# XoverVolume.net
KiCad netlist of a schematic drawn in EAGLE
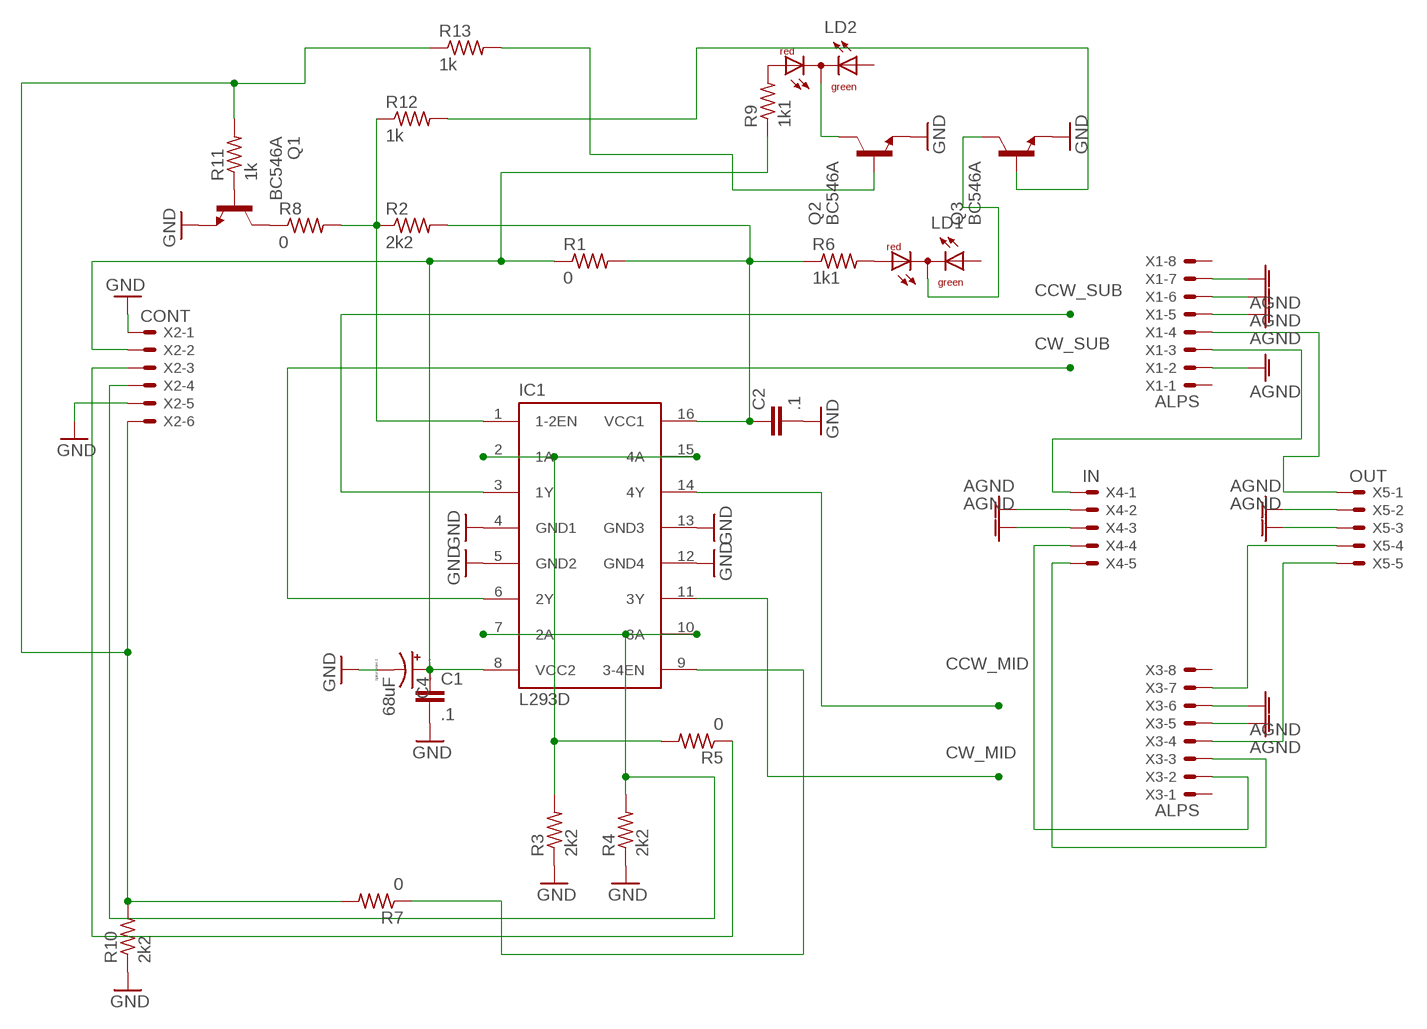
[diagram p0: schematic, sheet 1]

(export (version "E")
  (design (tool "Eeschema 10.0.6"))
  (components
    (comp (ref "C1")
      (value ".1")
      (footprint "eagle-import:C1210")
      (libsource (lib "eagle-import") (part "C-EUC1210"))
    )
    (comp (ref "C2")
      (value ".1")
      (footprint "eagle-import:C1210")
      (libsource (lib "eagle-import") (part "C-EUC1210"))
    )
    (comp (ref "C4")
      (value "68uF")
      (footprint "eagle-import:E2,5-6E")
      (libsource (lib "eagle-import") (part "CPOL-USE2,5-6E"))
    )
    (comp (ref "IC1")
      (value "L293D")
      (footprint "eagle-import:DIL16")
      (libsource (lib "eagle-import") (part "L293D"))
    )
    (comp (ref "LD1")
      (value "DUOLED-RG-C")
      (footprint "eagle-import:DUOLED-C-5MM")
      (libsource (lib "eagle-import") (part "DUOLED-RG-C"))
    )
    (comp (ref "LD2")
      (value "DUOLED-RG-C")
      (footprint "eagle-import:DUOLED-C-5MM")
      (libsource (lib "eagle-import") (part "DUOLED-RG-C"))
    )
    (comp (ref "Q1")
      (value "BC546A")
      (footprint "eagle-import:TO92-EBC")
      (libsource (lib "eagle-import") (part "BC546A"))
    )
    (comp (ref "Q2")
      (value "BC546A")
      (footprint "eagle-import:TO92-EBC")
      (libsource (lib "eagle-import") (part "BC546A"))
    )
    (comp (ref "Q3")
      (value "BC546A")
      (footprint "eagle-import:TO92-EBC")
      (libsource (lib "eagle-import") (part "BC546A"))
    )
    (comp (ref "R1")
      (value "0")
      (footprint "eagle-import:0207_15")
      (libsource (lib "eagle-import") (part "R-US_0207/15"))
    )
    (comp (ref "R2")
      (value "2k2")
      (footprint "eagle-import:R1210")
      (libsource (lib "eagle-import") (part "R-US_R1210"))
    )
    (comp (ref "R3")
      (value "2k2")
      (footprint "eagle-import:R1210")
      (libsource (lib "eagle-import") (part "R-US_R1210"))
    )
    (comp (ref "R4")
      (value "2k2")
      (footprint "eagle-import:R1210")
      (libsource (lib "eagle-import") (part "R-US_R1210"))
    )
    (comp (ref "R5")
      (value "0")
      (footprint "eagle-import:0309_12")
      (libsource (lib "eagle-import") (part "R-US_0309/12"))
    )
    (comp (ref "R6")
      (value "1k1")
      (footprint "eagle-import:0309_12")
      (libsource (lib "eagle-import") (part "R-US_0309/12"))
    )
    (comp (ref "R7")
      (value "0")
      (footprint "eagle-import:0309_12")
      (libsource (lib "eagle-import") (part "R-US_0309/12"))
    )
    (comp (ref "R8")
      (value "0")
      (footprint "eagle-import:0207_15")
      (libsource (lib "eagle-import") (part "R-US_0207/15"))
    )
    (comp (ref "R9")
      (value "1k1")
      (footprint "eagle-import:0309_12")
      (libsource (lib "eagle-import") (part "R-US_0309/12"))
    )
    (comp (ref "R10")
      (value "2k2")
      (footprint "eagle-import:R1210")
      (libsource (lib "eagle-import") (part "R-US_R1210"))
    )
    (comp (ref "R11")
      (value "1k")
      (footprint "eagle-import:0207_5V")
      (libsource (lib "eagle-import") (part "R-US_0207/5V"))
    )
    (comp (ref "R12")
      (value "1k")
      (footprint "eagle-import:0204_5")
      (libsource (lib "eagle-import") (part "R-US_0204/5"))
    )
    (comp (ref "R13")
      (value "1k")
      (footprint "eagle-import:R1210")
      (libsource (lib "eagle-import") (part "R-US_R1210"))
    )
    (comp (ref "X1")
      (value "ALPS")
      (footprint "eagle-import:22-23-2081")
      (fields (field (name "MF") "MOLEX") (field (name "MPN") "22-23-2081"))
      (libsource (lib "eagle-import") (part "22-23-2081"))
    )
    (comp (ref "X2")
      (value "CONT")
      (footprint "eagle-import:22-23-2061")
      (fields (field (name "MF") "MOLEX") (field (name "MPN") "22-23-2061"))
      (libsource (lib "eagle-import") (part "22-23-2061"))
    )
    (comp (ref "X3")
      (value "ALPS")
      (footprint "eagle-import:22-23-2081")
      (fields (field (name "MF") "MOLEX") (field (name "MPN") "22-23-2081"))
      (libsource (lib "eagle-import") (part "22-23-2081"))
    )
    (comp (ref "X4")
      (value "IN")
      (footprint "eagle-import:22-23-2051")
      (fields (field (name "MF") "MOLEX") (field (name "MPN") "22-23-2051"))
      (libsource (lib "eagle-import") (part "22-23-2051"))
    )
    (comp (ref "X5")
      (value "OUT")
      (footprint "eagle-import:22-23-2051")
      (fields (field (name "MF") "MOLEX") (field (name "MPN") "22-23-2051"))
      (libsource (lib "eagle-import") (part "22-23-2051"))
    )
  )
  (nets
    (net (code "1") (name "/CCW_MID") (class "Default")
      (node (ref "IC1") (pin "14") (pinfunction "4Y_14") (pintype "output"))
    )
    (net (code "2") (name "/CCW_SUB") (class "Default")
      (node (ref "IC1") (pin "3") (pinfunction "1Y_3") (pintype "output"))
    )
    (net (code "3") (name "/CW_MID") (class "Default")
      (node (ref "IC1") (pin "11") (pinfunction "3Y_11") (pintype "output"))
    )
    (net (code "4") (name "/CW_SUB") (class "Default")
      (node (ref "IC1") (pin "6") (pinfunction "2Y_6") (pintype "output"))
    )
    (net (code "5") (name "AGND") (class "Default")
      (node (ref "X1") (pin "2") (pinfunction "S_2") (pintype "passive"))
      (node (ref "X1") (pin "5") (pinfunction "S_5") (pintype "passive"))
      (node (ref "X1") (pin "6") (pinfunction "S_6") (pintype "passive"))
      (node (ref "X1") (pin "7") (pinfunction "S_7") (pintype "passive"))
      (node (ref "X3") (pin "5") (pinfunction "S_5") (pintype "passive"))
      (node (ref "X3") (pin "6") (pinfunction "S_6") (pintype "passive"))
      (node (ref "X4") (pin "2") (pinfunction "S_2") (pintype "passive"))
      (node (ref "X4") (pin "3") (pinfunction "S_3") (pintype "passive"))
      (node (ref "X5") (pin "2") (pinfunction "S_2") (pintype "passive"))
      (node (ref "X5") (pin "3") (pinfunction "S_3") (pintype "passive"))
    )
    (net (code "6") (name "GND") (class "Default")
      (node (ref "C1") (pin "2") (pinfunction "2_2") (pintype "passive"))
      (node (ref "C2") (pin "2") (pinfunction "2_2") (pintype "passive"))
      (node (ref "C4") (pin "-") (pinfunction "-_-") (pintype "passive"))
      (node (ref "IC1") (pin "12") (pinfunction "GND4_12") (pintype "power_in"))
      (node (ref "IC1") (pin "13") (pinfunction "GND3_13") (pintype "power_in"))
      (node (ref "IC1") (pin "4") (pinfunction "GND1_4") (pintype "power_in"))
      (node (ref "IC1") (pin "5") (pinfunction "GND2_5") (pintype "power_in"))
      (node (ref "Q1") (pin "E") (pinfunction "E_E") (pintype "passive"))
      (node (ref "Q2") (pin "E") (pinfunction "E_E") (pintype "passive"))
      (node (ref "Q3") (pin "E") (pinfunction "E_E") (pintype "passive"))
      (node (ref "R10") (pin "1") (pinfunction "1_1") (pintype "passive"))
      (node (ref "R3") (pin "1") (pinfunction "1_1") (pintype "passive"))
      (node (ref "R4") (pin "1") (pinfunction "1_1") (pintype "passive"))
      (node (ref "X2") (pin "1") (pinfunction "S_1") (pintype "passive"))
      (node (ref "X2") (pin "5") (pinfunction "S_5") (pintype "passive"))
    )
    (net (code "7") (name "Net-(IC1-1-2EN)") (class "Default")
      (node (ref "IC1") (pin "1") (pinfunction "1-2EN_1") (pintype "input"))
      (node (ref "R12") (pin "1") (pinfunction "1_1") (pintype "passive"))
      (node (ref "R2") (pin "1") (pinfunction "1_1") (pintype "passive"))
      (node (ref "R8") (pin "2") (pinfunction "2_2") (pintype "passive"))
    )
    (net (code "8") (name "Net-(IC1-1A)") (class "Default")
      (node (ref "IC1") (pin "15") (pinfunction "4A_15") (pintype "input"))
      (node (ref "IC1") (pin "2") (pinfunction "1A_2") (pintype "input"))
      (node (ref "R3") (pin "2") (pinfunction "2_2") (pintype "passive"))
      (node (ref "R5") (pin "2") (pinfunction "2_2") (pintype "passive"))
    )
    (net (code "9") (name "Net-(IC1-2A)") (class "Default")
      (node (ref "IC1") (pin "10") (pinfunction "3A_10") (pintype "input"))
      (node (ref "IC1") (pin "7") (pinfunction "2A_7") (pintype "input"))
      (node (ref "R4") (pin "2") (pinfunction "2_2") (pintype "passive"))
      (node (ref "X2") (pin "4") (pinfunction "S_4") (pintype "passive"))
    )
    (net (code "10") (name "Net-(IC1-3-4EN)") (class "Default")
      (node (ref "IC1") (pin "9") (pinfunction "3-4EN_9") (pintype "input"))
      (node (ref "R7") (pin "1") (pinfunction "1_1") (pintype "passive"))
    )
    (net (code "11") (name "Net-(IC1-VCC1)") (class "Default")
      (node (ref "C2") (pin "1") (pinfunction "1_1") (pintype "passive"))
      (node (ref "IC1") (pin "16") (pinfunction "VCC1_16") (pintype "power_in"))
      (node (ref "R1") (pin "2") (pinfunction "2_2") (pintype "passive"))
      (node (ref "R2") (pin "2") (pinfunction "2_2") (pintype "passive"))
      (node (ref "R6") (pin "1") (pinfunction "1_1") (pintype "passive"))
    )
    (net (code "12") (name "Net-(IC1-VCC2)") (class "Default")
      (node (ref "C1") (pin "1") (pinfunction "1_1") (pintype "passive"))
      (node (ref "C4") (pin "+") (pinfunction "+_+") (pintype "passive"))
      (node (ref "IC1") (pin "8") (pinfunction "VCC2_8") (pintype "power_in"))
      (node (ref "R1") (pin "1") (pinfunction "1_1") (pintype "passive"))
      (node (ref "R9") (pin "1") (pinfunction "1_1") (pintype "passive"))
      (node (ref "X2") (pin "2") (pinfunction "S_2") (pintype "passive"))
    )
    (net (code "13") (name "Net-(LD1-PadAR)") (class "Default")
      (node (ref "LD1") (pin "AR") (pinfunction "AR_AR") (pintype "passive"))
      (node (ref "R6") (pin "2") (pinfunction "2_2") (pintype "passive"))
    )
    (net (code "14") (name "Net-(LD1-PadC)") (class "Default")
      (node (ref "LD1") (pin "C") (pinfunction "C_C") (pintype "passive"))
      (node (ref "Q3") (pin "C") (pinfunction "C_C") (pintype "passive"))
    )
    (net (code "15") (name "Net-(LD2-PadAR)") (class "Default")
      (node (ref "LD2") (pin "AR") (pinfunction "AR_AR") (pintype "passive"))
      (node (ref "R9") (pin "2") (pinfunction "2_2") (pintype "passive"))
    )
    (net (code "16") (name "Net-(LD2-PadC)") (class "Default")
      (node (ref "LD2") (pin "C") (pinfunction "C_C") (pintype "passive"))
      (node (ref "Q2") (pin "C") (pinfunction "C_C") (pintype "passive"))
    )
    (net (code "17") (name "Net-(Q1-PadB)") (class "Default")
      (node (ref "Q1") (pin "B") (pinfunction "B_B") (pintype "passive"))
      (node (ref "R11") (pin "1") (pinfunction "1_1") (pintype "passive"))
    )
    (net (code "18") (name "Net-(Q1-PadC)") (class "Default")
      (node (ref "Q1") (pin "C") (pinfunction "C_C") (pintype "passive"))
      (node (ref "R8") (pin "1") (pinfunction "1_1") (pintype "passive"))
    )
    (net (code "19") (name "Net-(Q2-PadB)") (class "Default")
      (node (ref "Q2") (pin "B") (pinfunction "B_B") (pintype "passive"))
      (node (ref "R13") (pin "2") (pinfunction "2_2") (pintype "passive"))
    )
    (net (code "20") (name "Net-(Q3-PadB)") (class "Default")
      (node (ref "Q3") (pin "B") (pinfunction "B_B") (pintype "passive"))
      (node (ref "R12") (pin "2") (pinfunction "2_2") (pintype "passive"))
    )
    (net (code "21") (name "Net-(X1C-S)") (class "Default")
      (node (ref "X1") (pin "3") (pinfunction "S_3") (pintype "passive"))
      (node (ref "X4") (pin "1") (pinfunction "S_1") (pintype "passive"))
    )
    (net (code "22") (name "Net-(X1D-S)") (class "Default")
      (node (ref "X1") (pin "4") (pinfunction "S_4") (pintype "passive"))
      (node (ref "X5") (pin "1") (pinfunction "S_1") (pintype "passive"))
    )
    (net (code "23") (name "Net-(X2C-S)") (class "Default")
      (node (ref "R5") (pin "1") (pinfunction "1_1") (pintype "passive"))
      (node (ref "X2") (pin "3") (pinfunction "S_3") (pintype "passive"))
    )
    (net (code "24") (name "Net-(X2F-S)") (class "Default")
      (node (ref "R10") (pin "2") (pinfunction "2_2") (pintype "passive"))
      (node (ref "R11") (pin "2") (pinfunction "2_2") (pintype "passive"))
      (node (ref "R13") (pin "1") (pinfunction "1_1") (pintype "passive"))
      (node (ref "R7") (pin "2") (pinfunction "2_2") (pintype "passive"))
      (node (ref "X2") (pin "6") (pinfunction "S_6") (pintype "passive"))
    )
    (net (code "25") (name "Net-(X3B-S)") (class "Default")
      (node (ref "X3") (pin "2") (pinfunction "S_2") (pintype "passive"))
      (node (ref "X4") (pin "4") (pinfunction "S_4") (pintype "passive"))
    )
    (net (code "26") (name "Net-(X3C-S)") (class "Default")
      (node (ref "X3") (pin "3") (pinfunction "S_3") (pintype "passive"))
      (node (ref "X4") (pin "5") (pinfunction "S_5") (pintype "passive"))
    )
    (net (code "27") (name "Net-(X3D-S)") (class "Default")
      (node (ref "X3") (pin "4") (pinfunction "S_4") (pintype "passive"))
      (node (ref "X5") (pin "5") (pinfunction "S_5") (pintype "passive"))
    )
    (net (code "28") (name "Net-(X3G-S)") (class "Default")
      (node (ref "X3") (pin "7") (pinfunction "S_7") (pintype "passive"))
      (node (ref "X5") (pin "4") (pinfunction "S_4") (pintype "passive"))
    )
    (net (code "29") (name "unconnected-(LD1-AG-PadAX)") (class "Default")
      (node (ref "LD1") (pin "AX") (pinfunction "AG_AX") (pintype "passive"))
    )
    (net (code "30") (name "unconnected-(LD2-AG-PadAX)") (class "Default")
      (node (ref "LD2") (pin "AX") (pinfunction "AG_AX") (pintype "passive"))
    )
    (net (code "31") (name "unconnected-(X1A-S-Pad1)") (class "Default")
      (node (ref "X1") (pin "1") (pinfunction "S_1") (pintype "passive"))
    )
    (net (code "32") (name "unconnected-(X1H-S-Pad8)") (class "Default")
      (node (ref "X1") (pin "8") (pinfunction "S_8") (pintype "passive"))
    )
    (net (code "33") (name "unconnected-(X3A-S-Pad1)") (class "Default")
      (node (ref "X3") (pin "1") (pinfunction "S_1") (pintype "passive"))
    )
    (net (code "34") (name "unconnected-(X3H-S-Pad8)") (class "Default")
      (node (ref "X3") (pin "8") (pinfunction "S_8") (pintype "passive"))
    )
  )
)
